# servo_pwr.net
KiCad netlist of a schematic drawn in Altium Designer
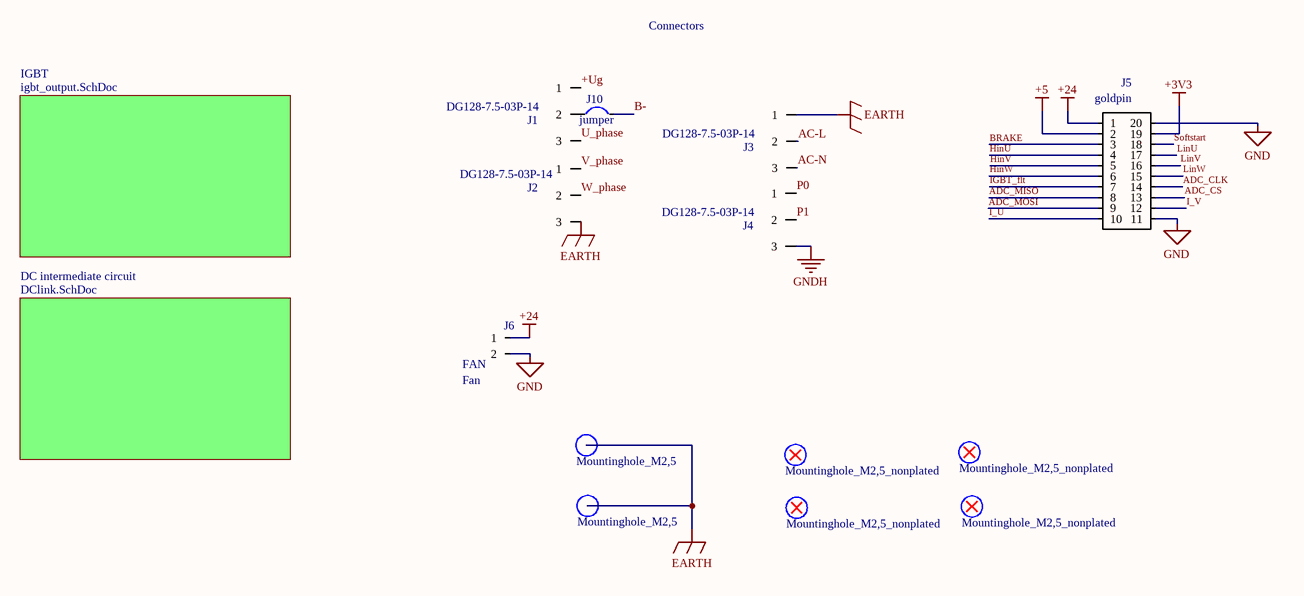
[diagram p0: servo_pwr.SchDoc]

(export (version "E")
  (design (tool "Eeschema 10.0.6"))
  (components
    (comp (ref "J1")
      (value "DG128-7.5-03P-14")
      (footprint "DG128-7.5-03P-14")
      (libsource (lib "connector") (part "DG128-7.5-03P-14"))
    )
    (comp (ref "J2")
      (value "DG128-7.5-03P-14")
      (footprint "DG128-7.5-03P-14")
      (libsource (lib "connector") (part "DG128-7.5-03P-14"))
    )
    (comp (ref "J3")
      (value "DG128-7.5-03P-14")
      (footprint "DG128-7.5-03P-14")
      (libsource (lib "connector") (part "DG128-7.5-03P-14"))
    )
    (comp (ref "J4")
      (value "DG128-7.5-03P-14")
      (footprint "DG128-7.5-03P-14")
      (libsource (lib "connector") (part "DG128-7.5-03P-14"))
    )
    (comp (ref "J5")
      (value "goldpin")
      (footprint "goldpin 2x10")
      (libsource (lib "connector") (part "goldpin"))
    )
    (comp (ref "J6") (value "FAN") (footprint "JST XH 2pin") (libsource (lib "jst 2pin") (part "JST 2pin")))
    (comp (ref "J10") (value "jumper") (footprint "Jumper") (libsource (lib "jumper") (part "jumper")))
    (comp (ref "MH3")
      (value "Mountinghole_M2,5")
      (footprint "Mountinghole M2,5")
      (libsource (lib "mountinghole") (part "Mountinghole_M2,5"))
    )
    (comp (ref "MH4")
      (value "Mountinghole_M2,5")
      (footprint "Mountinghole M2,5")
      (libsource (lib "mountinghole") (part "Mountinghole_M2,5"))
    )
    (comp (ref "MH5")
      (value "Mountinghole_M2,5_nonplated")
      (footprint "Mountinghole M2,5 non plated")
      (libsource (lib "mountinghole") (part "Mountinghole_M2,5_nonplated"))
    )
    (comp (ref "MH6")
      (value "Mountinghole_M2,5_nonplated")
      (footprint "Mountinghole M2,5 non plated")
      (libsource (lib "mountinghole") (part "Mountinghole_M2,5_nonplated"))
    )
    (comp (ref "MH7")
      (value "Mountinghole_M2,5_nonplated")
      (footprint "Mountinghole M2,5 non plated")
      (libsource (lib "mountinghole") (part "Mountinghole_M2,5_nonplated"))
    )
    (comp (ref "MH8")
      (value "Mountinghole_M2,5_nonplated")
      (footprint "Mountinghole M2,5 non plated")
      (libsource (lib "mountinghole") (part "Mountinghole_M2,5_nonplated"))
    )
  )
  (nets
    (net (code "1") (name "+3V3") (class "Default")
      (node (ref "J5") (pin "19") (pinfunction "19_19") (pintype "passive"))
    )
    (net (code "2") (name "+5") (class "Default")
      (node (ref "J5") (pin "2") (pinfunction "2_2") (pintype "passive"))
    )
    (net (code "3") (name "+24") (class "Default")
      (node (ref "J5") (pin "1") (pinfunction "1_1") (pintype "passive"))
      (node (ref "J6") (pin "1") (pinfunction "1_1") (pintype "passive"))
    )
    (net (code "4") (name "/+Ug") (class "Default")
      (node (ref "J1") (pin "1") (pinfunction "1_1") (pintype "passive"))
    )
    (net (code "5") (name "/AC-L") (class "Default")
      (node (ref "J3") (pin "2") (pinfunction "2_2") (pintype "passive"))
    )
    (net (code "6") (name "/AC-N") (class "Default")
      (node (ref "J3") (pin "3") (pinfunction "3_3") (pintype "passive"))
    )
    (net (code "7") (name "/ADC_CLK") (class "Default")
      (node (ref "J5") (pin "14") (pinfunction "14_14") (pintype "passive"))
    )
    (net (code "8") (name "/ADC_CS") (class "Default")
      (node (ref "J5") (pin "13") (pinfunction "13_13") (pintype "passive"))
    )
    (net (code "9") (name "/ADC_MISO") (class "Default")
      (node (ref "J5") (pin "8") (pinfunction "8_8") (pintype "passive"))
    )
    (net (code "10") (name "/ADC_MOSI") (class "Default")
      (node (ref "J5") (pin "9") (pinfunction "9_9") (pintype "passive"))
    )
    (net (code "11") (name "/B-") (class "Default")
      (node (ref "J10") (pin "1") (pinfunction "1_1") (pintype "passive"))
    )
    (net (code "12") (name "/BRAKE") (class "Default")
      (node (ref "J5") (pin "3") (pinfunction "3_3") (pintype "passive"))
    )
    (net (code "13") (name "/HinU") (class "Default")
      (node (ref "J5") (pin "4") (pinfunction "4_4") (pintype "passive"))
    )
    (net (code "14") (name "/HinV") (class "Default")
      (node (ref "J5") (pin "5") (pinfunction "5_5") (pintype "passive"))
    )
    (net (code "15") (name "/HinW") (class "Default")
      (node (ref "J5") (pin "6") (pinfunction "6_6") (pintype "passive"))
    )
    (net (code "16") (name "/IGBT_flt") (class "Default")
      (node (ref "J5") (pin "7") (pinfunction "7_7") (pintype "passive"))
    )
    (net (code "17") (name "/I_U") (class "Default")
      (node (ref "J5") (pin "10") (pinfunction "10_10") (pintype "passive"))
    )
    (net (code "18") (name "/I_V") (class "Default")
      (node (ref "J5") (pin "12") (pinfunction "12_12") (pintype "passive"))
    )
    (net (code "19") (name "/LinU") (class "Default")
      (node (ref "J5") (pin "17") (pinfunction "17_17") (pintype "passive"))
    )
    (net (code "20") (name "/LinV") (class "Default")
      (node (ref "J5") (pin "16") (pinfunction "16_16") (pintype "passive"))
    )
    (net (code "21") (name "/LinW") (class "Default")
      (node (ref "J5") (pin "15") (pinfunction "15_15") (pintype "passive"))
    )
    (net (code "22") (name "/P0") (class "Default")
      (node (ref "J4") (pin "1") (pinfunction "1_1") (pintype "passive"))
    )
    (net (code "23") (name "/P1") (class "Default")
      (node (ref "J4") (pin "2") (pinfunction "2_2") (pintype "passive"))
    )
    (net (code "24") (name "/Softstart") (class "Default")
      (node (ref "J5") (pin "18") (pinfunction "18_18") (pintype "passive"))
    )
    (net (code "25") (name "/U_phase") (class "Default")
      (node (ref "J1") (pin "3") (pinfunction "3_3") (pintype "passive"))
    )
    (net (code "26") (name "/V_phase") (class "Default")
      (node (ref "J2") (pin "1") (pinfunction "1_1") (pintype "passive"))
    )
    (net (code "27") (name "/W_phase") (class "Default")
      (node (ref "J2") (pin "2") (pinfunction "2_2") (pintype "passive"))
    )
    (net (code "28") (name "EARTH") (class "Default")
      (node (ref "J2") (pin "3") (pinfunction "3_3") (pintype "passive"))
      (node (ref "J3") (pin "1") (pinfunction "1_1") (pintype "passive"))
      (node (ref "MH3") (pin "1") (pinfunction "1_1") (pintype "passive"))
      (node (ref "MH4") (pin "1") (pinfunction "1_1") (pintype "passive"))
    )
    (net (code "29") (name "GND") (class "Default")
      (node (ref "J5") (pin "11") (pinfunction "11_11") (pintype "passive"))
      (node (ref "J5") (pin "20") (pinfunction "20_20") (pintype "passive"))
      (node (ref "J6") (pin "2") (pinfunction "2_2") (pintype "passive"))
    )
    (net (code "30") (name "GNDH") (class "Default")
      (node (ref "J4") (pin "3") (pinfunction "3_3") (pintype "passive"))
    )
    (net (code "31") (name "Net-(J1-Pad2)") (class "Default")
      (node (ref "J1") (pin "2") (pinfunction "2_2") (pintype "passive"))
      (node (ref "J10") (pin "2") (pinfunction "2_2") (pintype "passive"))
    )
    (net (code "32") (name "unconnected-(MH5-Pad1)") (class "Default")
      (node (ref "MH5") (pin "1") (pinfunction "1_1") (pintype "passive+no_connect"))
    )
    (net (code "33") (name "unconnected-(MH6-Pad1)") (class "Default")
      (node (ref "MH6") (pin "1") (pinfunction "1_1") (pintype "passive+no_connect"))
    )
    (net (code "34") (name "unconnected-(MH7-Pad1)") (class "Default")
      (node (ref "MH7") (pin "1") (pinfunction "1_1") (pintype "passive+no_connect"))
    )
    (net (code "35") (name "unconnected-(MH8-Pad1)") (class "Default")
      (node (ref "MH8") (pin "1") (pinfunction "1_1") (pintype "passive+no_connect"))
    )
  )
)
